# salumi.net
KiCad netlist of a schematic drawn in EAGLE
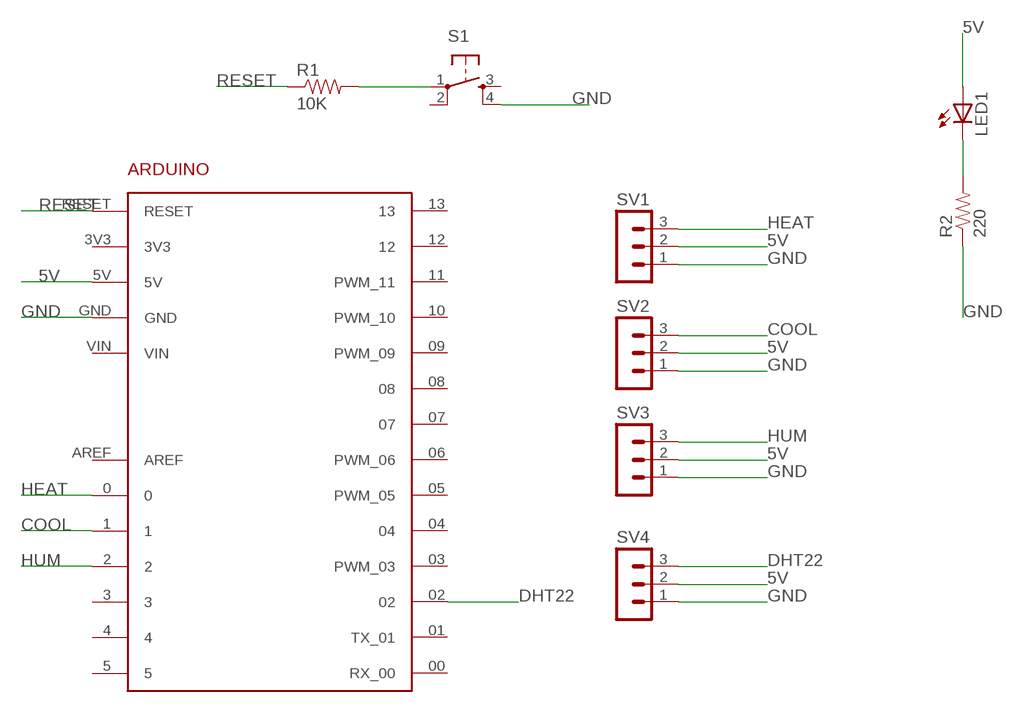
[diagram p0: schematic, sheet 1]

(export (version "E")
  (design (tool "Eeschema 10.0.6"))
  (components
    (comp (ref "ARDUINO1")
      (value "ARDUINO")
      (footprint "eagle-import:ARDUINO")
      (libsource (lib "eagle-import") (part "ARDUINO"))
    )
    (comp (ref "LED1")
      (value "LED5MM")
      (footprint "eagle-import:LED5MM")
      (libsource (lib "eagle-import") (part "LED5MM"))
    )
    (comp (ref "R1")
      (value "10K")
      (footprint "eagle-import:AXIAL-0.3")
      (libsource (lib "eagle-import") (part "RESISTORAXIAL-0.3"))
    )
    (comp (ref "R2")
      (value "220")
      (footprint "eagle-import:AXIAL-0.3")
      (libsource (lib "eagle-import") (part "RESISTORAXIAL-0.3"))
    )
    (comp (ref "S1")
      (value "TAC_SWITCHPTH")
      (footprint "eagle-import:TACTILE-PTH")
      (libsource (lib "eagle-import") (part "TAC_SWITCHPTH"))
    )
    (comp (ref "SV1")
      (value "MA03-1")
      (footprint "eagle-import:MA03-1")
      (libsource (lib "eagle-import") (part "MA03-1"))
    )
    (comp (ref "SV2")
      (value "MA03-1")
      (footprint "eagle-import:MA03-1")
      (libsource (lib "eagle-import") (part "MA03-1"))
    )
    (comp (ref "SV3")
      (value "MA03-1")
      (footprint "eagle-import:MA03-1")
      (libsource (lib "eagle-import") (part "MA03-1"))
    )
    (comp (ref "SV4")
      (value "MA03-1")
      (footprint "eagle-import:MA03-1")
      (libsource (lib "eagle-import") (part "MA03-1"))
    )
  )
  (nets
    (net (code "1") (name "/5V") (class "Default")
      (node (ref "ARDUINO1") (pin "5V") (pinfunction "5V_5V") (pintype "bidirectional"))
      (node (ref "LED1") (pin "A") (pinfunction "A_A") (pintype "passive"))
      (node (ref "SV1") (pin "2") (pinfunction "2_2") (pintype "passive"))
      (node (ref "SV2") (pin "2") (pinfunction "2_2") (pintype "passive"))
      (node (ref "SV3") (pin "2") (pinfunction "2_2") (pintype "passive"))
      (node (ref "SV4") (pin "2") (pinfunction "2_2") (pintype "passive"))
    )
    (net (code "2") (name "/COOL") (class "Default")
      (node (ref "ARDUINO1") (pin "1") (pinfunction "1_1") (pintype "bidirectional"))
      (node (ref "SV2") (pin "3") (pinfunction "3_3") (pintype "passive"))
    )
    (net (code "3") (name "/DHT22") (class "Default")
      (node (ref "ARDUINO1") (pin "02") (pinfunction "02_02") (pintype "bidirectional"))
      (node (ref "SV4") (pin "3") (pinfunction "3_3") (pintype "passive"))
    )
    (net (code "4") (name "/GND") (class "Default")
      (node (ref "ARDUINO1") (pin "GND") (pinfunction "GND_GND") (pintype "bidirectional"))
      (node (ref "R2") (pin "P$1") (pinfunction "1_P$1") (pintype "passive"))
      (node (ref "S1") (pin "4") (pinfunction "4_4") (pintype "passive"))
      (node (ref "SV1") (pin "1") (pinfunction "1_1") (pintype "passive"))
      (node (ref "SV2") (pin "1") (pinfunction "1_1") (pintype "passive"))
      (node (ref "SV3") (pin "1") (pinfunction "1_1") (pintype "passive"))
      (node (ref "SV4") (pin "1") (pinfunction "1_1") (pintype "passive"))
    )
    (net (code "5") (name "/HEAT") (class "Default")
      (node (ref "ARDUINO1") (pin "0") (pinfunction "0_0") (pintype "bidirectional"))
      (node (ref "SV1") (pin "3") (pinfunction "3_3") (pintype "passive"))
    )
    (net (code "6") (name "/HUM") (class "Default")
      (node (ref "ARDUINO1") (pin "2") (pinfunction "2_2") (pintype "bidirectional"))
      (node (ref "SV3") (pin "3") (pinfunction "3_3") (pintype "passive"))
    )
    (net (code "7") (name "/RESET") (class "Default")
      (node (ref "ARDUINO1") (pin "RESET") (pinfunction "RESET_RESET") (pintype "bidirectional"))
      (node (ref "R1") (pin "P$1") (pinfunction "1_P$1") (pintype "passive"))
    )
    (net (code "8") (name "Net-(LED1-C)") (class "Default")
      (node (ref "LED1") (pin "K") (pinfunction "C_K") (pintype "passive"))
      (node (ref "R2") (pin "P$2") (pinfunction "2_P$2") (pintype "passive"))
    )
    (net (code "9") (name "Net-(R1-2)") (class "Default")
      (node (ref "R1") (pin "P$2") (pinfunction "2_P$2") (pintype "passive"))
      (node (ref "S1") (pin "1") (pinfunction "1_1") (pintype "passive"))
    )
    (net (code "10") (name "unconnected-(ARDUINO1-PWM_03-Pad03)") (class "Default")
      (node (ref "ARDUINO1") (pin "03") (pinfunction "PWM_03_03") (pintype "bidirectional"))
    )
    (net (code "11") (name "unconnected-(ARDUINO1-PWM_05-Pad05)") (class "Default")
      (node (ref "ARDUINO1") (pin "05") (pinfunction "PWM_05_05") (pintype "bidirectional"))
    )
    (net (code "12") (name "unconnected-(ARDUINO1-PWM_06-Pad06)") (class "Default")
      (node (ref "ARDUINO1") (pin "06") (pinfunction "PWM_06_06") (pintype "bidirectional"))
    )
    (net (code "13") (name "unconnected-(ARDUINO1-PWM_09-Pad09)") (class "Default")
      (node (ref "ARDUINO1") (pin "09") (pinfunction "PWM_09_09") (pintype "bidirectional"))
    )
    (net (code "14") (name "unconnected-(ARDUINO1-PWM_10-Pad10)") (class "Default")
      (node (ref "ARDUINO1") (pin "10") (pinfunction "PWM_10_10") (pintype "bidirectional"))
    )
    (net (code "15") (name "unconnected-(ARDUINO1-PWM_11-Pad11)") (class "Default")
      (node (ref "ARDUINO1") (pin "11") (pinfunction "PWM_11_11") (pintype "bidirectional"))
    )
    (net (code "16") (name "unconnected-(ARDUINO1-Pad3)") (class "Default")
      (node (ref "ARDUINO1") (pin "3") (pinfunction "3_3") (pintype "bidirectional"))
    )
    (net (code "17") (name "unconnected-(ARDUINO1-Pad3V3)") (class "Default")
      (node (ref "ARDUINO1") (pin "3V3") (pinfunction "3V3_3V3") (pintype "bidirectional"))
    )
    (net (code "18") (name "unconnected-(ARDUINO1-Pad04)") (class "Default")
      (node (ref "ARDUINO1") (pin "04") (pinfunction "04_04") (pintype "bidirectional"))
    )
    (net (code "19") (name "unconnected-(ARDUINO1-Pad4)") (class "Default")
      (node (ref "ARDUINO1") (pin "4") (pinfunction "4_4") (pintype "bidirectional"))
    )
    (net (code "20") (name "unconnected-(ARDUINO1-Pad5)") (class "Default")
      (node (ref "ARDUINO1") (pin "5") (pinfunction "5_5") (pintype "bidirectional"))
    )
    (net (code "21") (name "unconnected-(ARDUINO1-Pad07)") (class "Default")
      (node (ref "ARDUINO1") (pin "07") (pinfunction "07_07") (pintype "bidirectional"))
    )
    (net (code "22") (name "unconnected-(ARDUINO1-Pad08)") (class "Default")
      (node (ref "ARDUINO1") (pin "08") (pinfunction "08_08") (pintype "bidirectional"))
    )
    (net (code "23") (name "unconnected-(ARDUINO1-Pad12)") (class "Default")
      (node (ref "ARDUINO1") (pin "12") (pinfunction "12_12") (pintype "bidirectional"))
    )
    (net (code "24") (name "unconnected-(ARDUINO1-Pad13)") (class "Default")
      (node (ref "ARDUINO1") (pin "13") (pinfunction "13_13") (pintype "bidirectional"))
    )
    (net (code "25") (name "unconnected-(ARDUINO1-PadAREF)") (class "Default")
      (node (ref "ARDUINO1") (pin "AREF") (pinfunction "AREF_AREF") (pintype "bidirectional"))
    )
    (net (code "26") (name "unconnected-(ARDUINO1-PadVIN)") (class "Default")
      (node (ref "ARDUINO1") (pin "VIN") (pinfunction "VIN_VIN") (pintype "bidirectional"))
    )
    (net (code "27") (name "unconnected-(ARDUINO1-RX_00-Pad00)") (class "Default")
      (node (ref "ARDUINO1") (pin "00") (pinfunction "RX_00_00") (pintype "bidirectional"))
    )
    (net (code "28") (name "unconnected-(ARDUINO1-TX_01-Pad01)") (class "Default")
      (node (ref "ARDUINO1") (pin "01") (pinfunction "TX_01_01") (pintype "bidirectional"))
    )
    (net (code "29") (name "unconnected-(S1-Pad2)") (class "Default")
      (node (ref "S1") (pin "2") (pinfunction "2_2") (pintype "passive"))
    )
    (net (code "30") (name "unconnected-(S1-Pad3)") (class "Default")
      (node (ref "S1") (pin "3") (pinfunction "3_3") (pintype "passive"))
    )
  )
)
